# l297_l298.net
KiCad netlist of a schematic drawn in Altium Designer
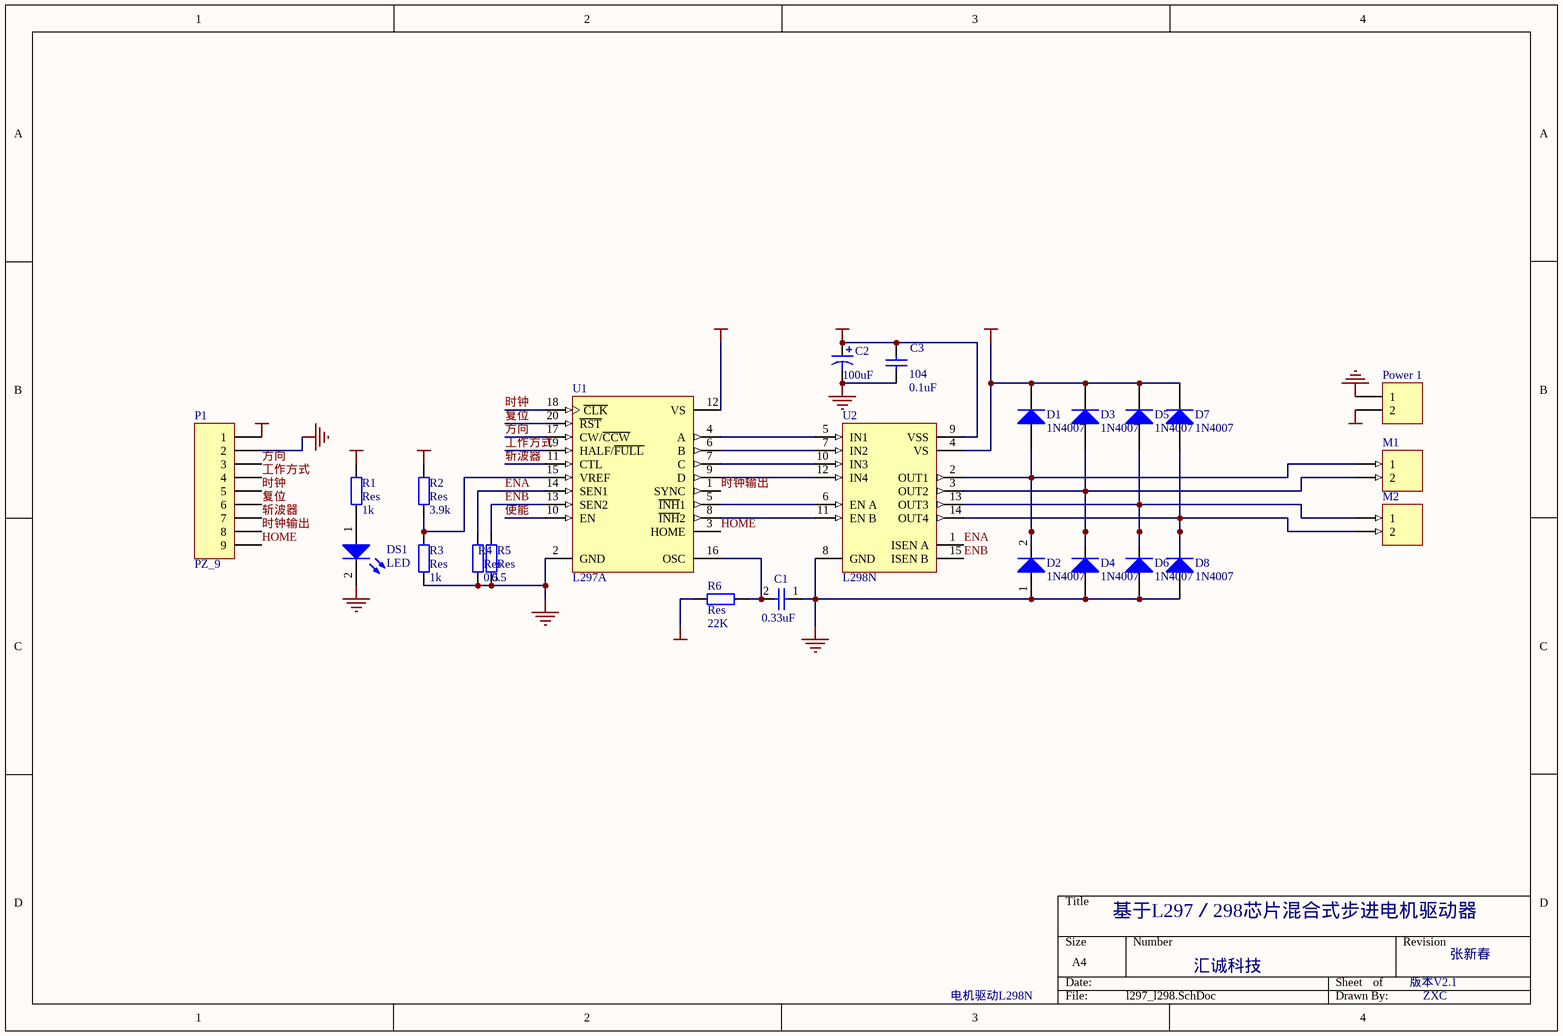
[diagram p0: l297_l298.SchDoc]

(export (version "E")
  (design (tool "Eeschema 10.0.6"))
  (components
    (comp (ref "C1")
      (value "0.33uF")
      (footprint "C-DJ-4")
      (description "Capacitor")
      (fields (field (name "PUBLISHER") "Altium Limited"))
      (libsource (lib "") (part "Cap_1"))
    )
    (comp (ref "C2")
      (value "100uF")
      (footprint "C-DJ-6")
      (description "Polarized Capacitor (Surface Mount)")
      (fields (field (name "PUBLISHER") "Altium Limited"))
      (libsource (lib "Miscellaneous Devices") (part "Cap Pol3"))
    )
    (comp (ref "C3")
      (value "104")
      (footprint "CPDR")
      (description "Capacitor")
      (fields (field (name "ALTIUM_VALUE") "0.1uF") (field (name "PUBLISHER") "Altium Limited"))
      (libsource (lib "Miscellaneous Devices") (part "Cap"))
    )
    (comp (ref "D1")
      (value "1N4007")
      (footprint "D-ZL-10")
      (description "1 Amp General Purpose Rectifier")
      (fields (field (name "PUBLISHER") "Altium Limited"))
      (libsource (lib "Miscellaneous Devices") (part "Diode 1N4007"))
    )
    (comp (ref "D2")
      (value "1N4007")
      (footprint "D-ZL-10")
      (description "1 Amp General Purpose Rectifier")
      (fields (field (name "PUBLISHER") "Altium Limited"))
      (libsource (lib "") (part "Diode 1N4007_1"))
    )
    (comp (ref "D3")
      (value "1N4007")
      (footprint "D-ZL-10")
      (description "1 Amp General Purpose Rectifier")
      (fields (field (name "PUBLISHER") "Altium Limited"))
      (libsource (lib "Miscellaneous Devices") (part "Diode 1N4007"))
    )
    (comp (ref "D4")
      (value "1N4007")
      (footprint "D-ZL-10")
      (description "1 Amp General Purpose Rectifier")
      (fields (field (name "PUBLISHER") "Altium Limited"))
      (libsource (lib "Miscellaneous Devices") (part "Diode 1N4007"))
    )
    (comp (ref "D5")
      (value "1N4007")
      (footprint "D-ZL-10")
      (description "1 Amp General Purpose Rectifier")
      (fields (field (name "PUBLISHER") "Altium Limited"))
      (libsource (lib "Miscellaneous Devices") (part "Diode 1N4007"))
    )
    (comp (ref "D6")
      (value "1N4007")
      (footprint "D-ZL-10")
      (description "1 Amp General Purpose Rectifier")
      (fields (field (name "PUBLISHER") "Altium Limited"))
      (libsource (lib "Miscellaneous Devices") (part "Diode 1N4007"))
    )
    (comp (ref "D7")
      (value "1N4007")
      (footprint "D-ZL-10")
      (description "1 Amp General Purpose Rectifier")
      (fields (field (name "PUBLISHER") "Altium Limited"))
      (libsource (lib "Miscellaneous Devices") (part "Diode 1N4007"))
    )
    (comp (ref "D8")
      (value "1N4007")
      (footprint "D-ZL-10")
      (description "1 Amp General Purpose Rectifier")
      (fields (field (name "PUBLISHER") "Altium Limited"))
      (libsource (lib "Miscellaneous Devices") (part "Diode 1N4007"))
    )
    (comp (ref "DS1")
      (value "LED")
      (footprint "CPDR")
      (description "发光二极管")
      (fields (field (name "PUBLISHER") "Altium Limited"))
      (libsource (lib "zxcourhc") (part "LED"))
    )
    (comp (ref "M1")
      (value "~")
      (footprint "JK128")
      (description "Header, 2-Pin")
      (fields (field (name "PUBLISHER") "Altium Limited"))
      (libsource (lib "Miscellaneous Connectors") (part "MHDR1X2"))
    )
    (comp (ref "M2")
      (value "~")
      (footprint "JK128")
      (description "Header, 2-Pin")
      (fields (field (name "PUBLISHER") "Altium Limited"))
      (libsource (lib "Miscellaneous Connectors") (part "MHDR1X2"))
    )
    (comp (ref "P1")
      (value "PZ_9")
      (footprint "HDR-9")
      (description "排针——9")
      (fields (field (name "PUBLISHER") "Altium Limited"))
      (libsource (lib "zxcourhc") (part "PZ_9"))
    )
    (comp (ref "Power 1")
      (value "~")
      (footprint "JK128")
      (description "Header, 2-Pin")
      (fields (field (name "PUBLISHER") "Altium Limited"))
      (libsource (lib "Miscellaneous Connectors") (part "MHDR1X2"))
    )
    (comp (ref "R1")
      (value "Res")
      (footprint "zxcourhc:CPDR")
      (description "电阻")
      (fields (field (name "ALTIUM_VALUE") "1k") (field (name "PUBLISHER") "Altium Limited"))
      (libsource (lib "zxcourhc") (part "Res"))
    )
    (comp (ref "R2")
      (value "Res")
      (footprint "zxcourhc:CPDR")
      (description "电阻")
      (fields (field (name "ALTIUM_VALUE") "3.9k") (field (name "PUBLISHER") "Altium Limited"))
      (libsource (lib "zxcourhc") (part "Res"))
    )
    (comp (ref "R3")
      (value "Res")
      (footprint "CPDR")
      (description "电阻")
      (fields (field (name "ALTIUM_VALUE") "1k") (field (name "PUBLISHER") "Altium Limited"))
      (libsource (lib "zxcourhc") (part "Res"))
    )
    (comp (ref "R4")
      (value "Res")
      (footprint "ZCDZl")
      (description "电阻")
      (fields (field (name "ALTIUM_VALUE") "0.5") (field (name "PUBLISHER") "Altium Limited"))
      (libsource (lib "zxcourhc") (part "Res"))
    )
    (comp (ref "R5")
      (value "Res")
      (footprint "ZCDZl")
      (description "电阻")
      (fields (field (name "ALTIUM_VALUE") "0.5") (field (name "PUBLISHER") "Altium Limited"))
      (libsource (lib "zxcourhc") (part "Res"))
    )
    (comp (ref "R6")
      (value "Res")
      (footprint "CPDR")
      (description "电阻")
      (fields (field (name "ALTIUM_VALUE") "22K") (field (name "PUBLISHER") "Altium Limited"))
      (libsource (lib "") (part "Res_1"))
    )
    (comp (ref "U1")
      (value "L297A")
      (footprint "DIP20")
      (description "Stepper Motor Controller")
      (fields (field (name "PUBLISHER") "Altium Limited"))
      (libsource (lib "ST Interface Stepper Motor Controller") (part "L297A"))
    )
    (comp (ref "U2")
      (value "L298N")
      (footprint "zxcourhc:L298N")
      (description "Dual Full Bridge Driver")
      (fields (field (name "PUBLISHER") "Altium Limited"))
      (libsource (lib "ST Interface DC Motor Controller") (part "L298N"))
    )
  )
  (nets
    (net (code "1") (name "+5V") (class "Default")
      (node (ref "C2") (pin "1") (pinfunction "1_1") (pintype "passive"))
      (node (ref "C3") (pin "2") (pinfunction "2_2") (pintype "passive"))
      (node (ref "P1") (pin "1") (pinfunction "1_1") (pintype "passive"))
      (node (ref "R1") (pin "1") (pinfunction "1_1") (pintype "passive"))
      (node (ref "R2") (pin "1") (pinfunction "1_1") (pintype "passive"))
      (node (ref "R6") (pin "2") (pinfunction "2_2") (pintype "passive"))
      (node (ref "U1") (pin "12") (pinfunction "VS_12") (pintype "power_in"))
      (node (ref "U2") (pin "9") (pinfunction "VSS_9") (pintype "power_in"))
    )
    (net (code "2") (name "/ENA") (class "Default")
      (node (ref "R4") (pin "1") (pinfunction "1_1") (pintype "passive"))
      (node (ref "U1") (pin "14") (pinfunction "SEN1_14") (pintype "input"))
      (node (ref "U2") (pin "1") (pinfunction "ISEN_A_1") (pintype "passive"))
    )
    (net (code "3") (name "/ENB") (class "Default")
      (node (ref "R5") (pin "1") (pinfunction "1_1") (pintype "passive"))
      (node (ref "U1") (pin "13") (pinfunction "SEN2_13") (pintype "input"))
      (node (ref "U2") (pin "15") (pinfunction "ISEN_B_15") (pintype "passive"))
    )
    (net (code "4") (name "/HOME") (class "Default")
      (node (ref "P1") (pin "9") (pinfunction "9_9") (pintype "passive"))
      (node (ref "U1") (pin "3") (pinfunction "HOME_3") (pintype "open_collector"))
    )
    (net (code "5") (name "/使能") (class "Default")
      (node (ref "U1") (pin "10") (pinfunction "EN_10") (pintype "input"))
    )
    (net (code "6") (name "/复位") (class "Default")
      (node (ref "P1") (pin "6") (pinfunction "6_6") (pintype "passive"))
      (node (ref "U1") (pin "20") (pinfunction "~{RST}_20") (pintype "input"))
    )
    (net (code "7") (name "/工作方式") (class "Default")
      (node (ref "P1") (pin "4") (pinfunction "4_4") (pintype "passive"))
      (node (ref "U1") (pin "19") (pinfunction "HALF/~{FULL}_19") (pintype "input"))
    )
    (net (code "8") (name "/斩波器") (class "Default")
      (node (ref "P1") (pin "7") (pinfunction "7_7") (pintype "passive"))
      (node (ref "U1") (pin "11") (pinfunction "CTL_11") (pintype "input"))
    )
    (net (code "9") (name "/方向") (class "Default")
      (node (ref "P1") (pin "3") (pinfunction "3_3") (pintype "passive"))
      (node (ref "U1") (pin "17") (pinfunction "CW/~{CCW}_17") (pintype "input"))
    )
    (net (code "10") (name "/时钟") (class "Default")
      (node (ref "P1") (pin "5") (pinfunction "5_5") (pintype "passive"))
      (node (ref "U1") (pin "18") (pinfunction "~{CLK}_18") (pintype "input"))
    )
    (net (code "11") (name "/时钟输出") (class "Default")
      (node (ref "P1") (pin "8") (pinfunction "8_8") (pintype "passive"))
      (node (ref "U1") (pin "1") (pinfunction "SYNC_1") (pintype "output"))
    )
    (net (code "12") (name "GND") (class "Default")
      (node (ref "C2") (pin "2") (pinfunction "2_2") (pintype "passive"))
      (node (ref "C3") (pin "1") (pinfunction "1_1") (pintype "passive"))
      (node (ref "DS1") (pin "2") (pinfunction "K_2") (pintype "passive"))
      (node (ref "P1") (pin "2") (pinfunction "2_2") (pintype "passive"))
      (node (ref "Power 1") (pin "1") (pinfunction "1_1") (pintype "power_in"))
      (node (ref "R3") (pin "2") (pinfunction "2_2") (pintype "passive"))
      (node (ref "R4") (pin "2") (pinfunction "2_2") (pintype "passive"))
      (node (ref "R5") (pin "2") (pinfunction "2_2") (pintype "passive"))
      (node (ref "U1") (pin "2") (pinfunction "GND_2") (pintype "power_in"))
    )
    (net (code "13") (name "GND-12") (class "Default")
      (node (ref "C1") (pin "1") (pinfunction "1_1") (pintype "passive"))
      (node (ref "D2") (pin "1") (pinfunction "A_1") (pintype "passive"))
      (node (ref "D4") (pin "1") (pinfunction "A_1") (pintype "passive"))
      (node (ref "D6") (pin "1") (pinfunction "A_1") (pintype "passive"))
      (node (ref "D8") (pin "1") (pinfunction "A_1") (pintype "passive"))
      (node (ref "U2") (pin "8") (pinfunction "GND_8") (pintype "power_in"))
    )
    (net (code "14") (name "Net-(D1-A)") (class "Default")
      (node (ref "D1") (pin "1") (pinfunction "A_1") (pintype "passive"))
      (node (ref "D2") (pin "2") (pinfunction "K_2") (pintype "passive"))
      (node (ref "M1") (pin "1") (pinfunction "1_1") (pintype "power_in"))
      (node (ref "U2") (pin "2") (pinfunction "OUT1_2") (pintype "output"))
    )
    (net (code "15") (name "Net-(D3-A)") (class "Default")
      (node (ref "D3") (pin "1") (pinfunction "A_1") (pintype "passive"))
      (node (ref "D4") (pin "2") (pinfunction "K_2") (pintype "passive"))
      (node (ref "M1") (pin "2") (pinfunction "2_2") (pintype "power_in"))
      (node (ref "U2") (pin "3") (pinfunction "OUT2_3") (pintype "output"))
    )
    (net (code "16") (name "Net-(D5-A)") (class "Default")
      (node (ref "D5") (pin "1") (pinfunction "A_1") (pintype "passive"))
      (node (ref "D6") (pin "2") (pinfunction "K_2") (pintype "passive"))
      (node (ref "M2") (pin "1") (pinfunction "1_1") (pintype "power_in"))
      (node (ref "U2") (pin "13") (pinfunction "OUT3_13") (pintype "output"))
    )
    (net (code "17") (name "Net-(D7-A)") (class "Default")
      (node (ref "D7") (pin "1") (pinfunction "A_1") (pintype "passive"))
      (node (ref "D8") (pin "2") (pinfunction "K_2") (pintype "passive"))
      (node (ref "M2") (pin "2") (pinfunction "2_2") (pintype "power_in"))
      (node (ref "U2") (pin "14") (pinfunction "OUT4_14") (pintype "output"))
    )
    (net (code "18") (name "Net-(DS1-A)") (class "Default")
      (node (ref "DS1") (pin "1") (pinfunction "A_1") (pintype "passive"))
      (node (ref "R1") (pin "2") (pinfunction "2_2") (pintype "passive"))
    )
    (net (code "19") (name "Net-(U1-A)") (class "Default")
      (node (ref "U1") (pin "4") (pinfunction "A_4") (pintype "output"))
      (node (ref "U2") (pin "5") (pinfunction "IN1_5") (pintype "input"))
    )
    (net (code "20") (name "Net-(U1-B)") (class "Default")
      (node (ref "U1") (pin "6") (pinfunction "B_6") (pintype "output"))
      (node (ref "U2") (pin "7") (pinfunction "IN2_7") (pintype "input"))
    )
    (net (code "21") (name "Net-(U1-C)") (class "Default")
      (node (ref "U1") (pin "7") (pinfunction "C_7") (pintype "output"))
      (node (ref "U2") (pin "10") (pinfunction "IN3_10") (pintype "input"))
    )
    (net (code "22") (name "Net-(U1-D)") (class "Default")
      (node (ref "U1") (pin "9") (pinfunction "D_9") (pintype "output"))
      (node (ref "U2") (pin "12") (pinfunction "IN4_12") (pintype "input"))
    )
    (net (code "23") (name "Net-(U1-OSC)") (class "Default")
      (node (ref "C1") (pin "2") (pinfunction "2_2") (pintype "passive"))
      (node (ref "R6") (pin "1") (pinfunction "1_1") (pintype "passive"))
      (node (ref "U1") (pin "16") (pinfunction "OSC_16") (pintype "passive"))
    )
    (net (code "24") (name "Net-(U1-VREF)") (class "Default")
      (node (ref "R2") (pin "2") (pinfunction "2_2") (pintype "passive"))
      (node (ref "R3") (pin "1") (pinfunction "1_1") (pintype "passive"))
      (node (ref "U1") (pin "15") (pinfunction "VREF_15") (pintype "input"))
    )
    (net (code "25") (name "Net-(U1-~{INH}1)") (class "Default")
      (node (ref "U1") (pin "5") (pinfunction "~{INH}1_5") (pintype "output"))
      (node (ref "U2") (pin "6") (pinfunction "EN_A_6") (pintype "input"))
    )
    (net (code "26") (name "Net-(U1-~{INH}2)") (class "Default")
      (node (ref "U1") (pin "8") (pinfunction "~{INH}2_8") (pintype "output"))
      (node (ref "U2") (pin "11") (pinfunction "EN_B_11") (pintype "input"))
    )
    (net (code "27") (name "VCC") (class "Default")
      (node (ref "D1") (pin "2") (pinfunction "K_2") (pintype "passive"))
      (node (ref "D3") (pin "2") (pinfunction "K_2") (pintype "passive"))
      (node (ref "D5") (pin "2") (pinfunction "K_2") (pintype "passive"))
      (node (ref "D7") (pin "2") (pinfunction "K_2") (pintype "passive"))
      (node (ref "Power 1") (pin "2") (pinfunction "2_2") (pintype "power_in"))
      (node (ref "U2") (pin "4") (pinfunction "VS_4") (pintype "power_in"))
    )
  )
)
